# SOM_IO1.net
KiCad netlist of a schematic drawn in Altium Designer
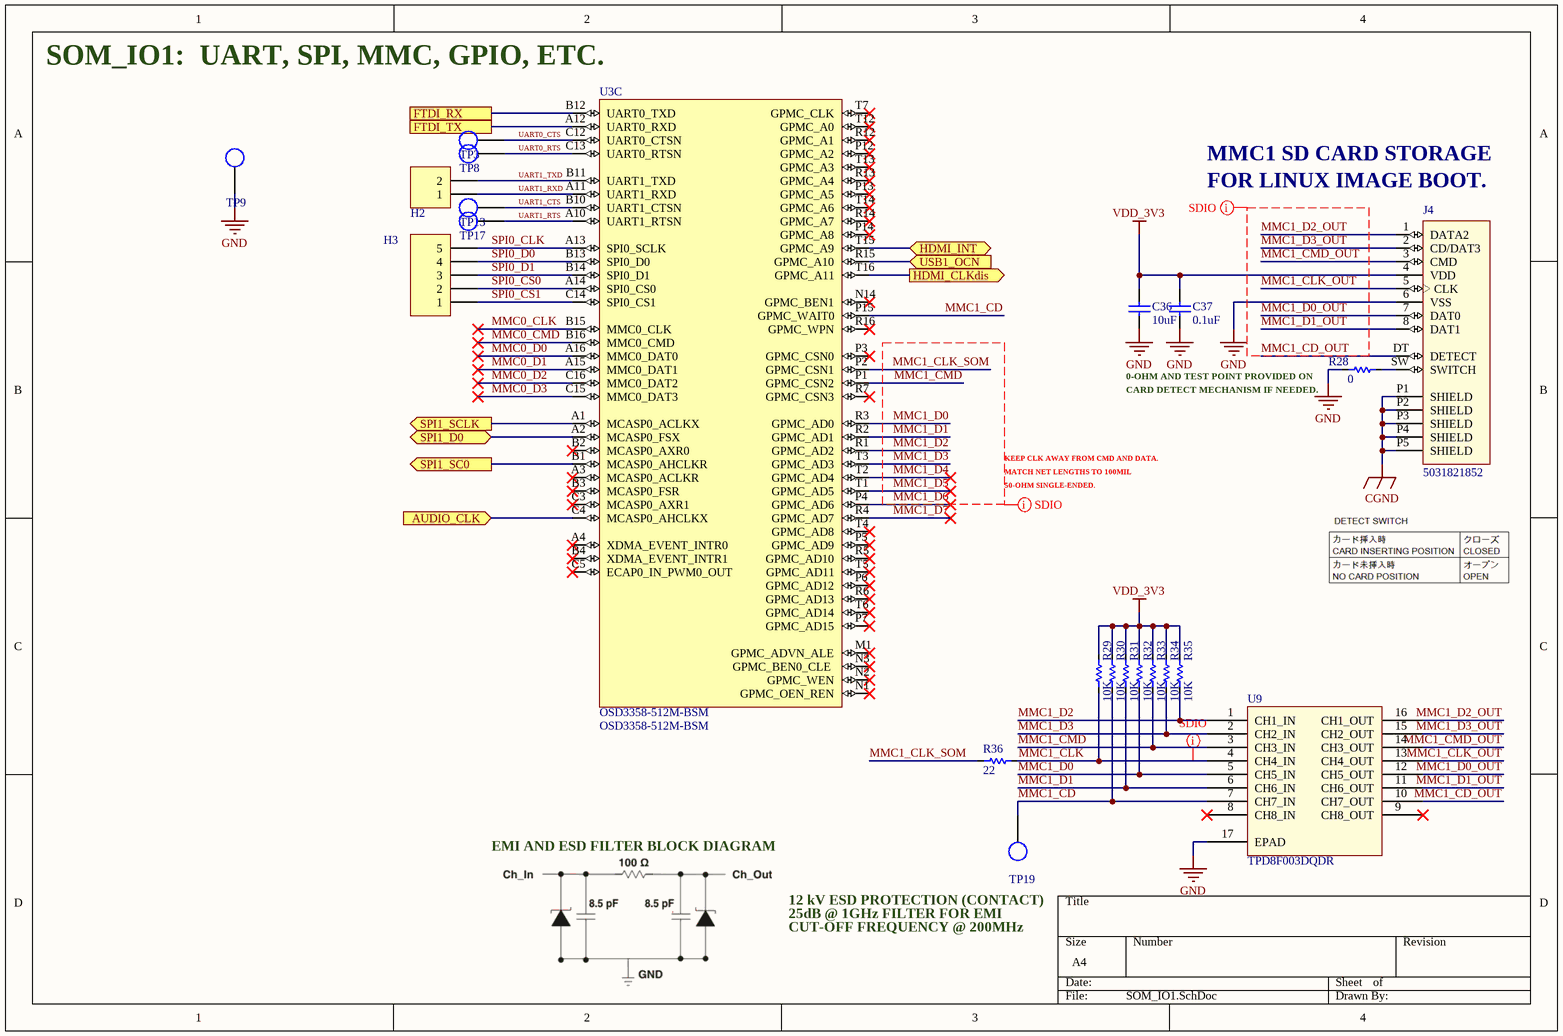
[diagram p0: SOM_IO1.SchDoc]

(export (version "E")
  (design (tool "Eeschema 10.0.6"))
  (components
    (comp (ref "C36")
      (value "10uF")
      (footprint "CAP_0603")
      (description "CAP CER 10UF 10V X5R 0603")
      (fields
        (field (name "MANUFACTURER") "KEMET")
        (field (name "MANUFACTURER PART NO.") "C0603C106M8PAC7867")
      )
      (libsource (lib "OSD335-X_Devboard") (part "C0603C106M8PAC7867"))
    )
    (comp (ref "C37")
      (value "0.1uF")
      (footprint "CAP_0603")
      (description "CAP CER 0.1UF 16V X7R 0603")
      (fields (field (name "MANUFACTURER") "KEMET") (field (name "MANUFACTURER PART NO.") "C0603C104M4RACTU"))
      (libsource (lib "OSD335-X_Devboard") (part "C0603C104M4RACTU"))
    )
    (comp (ref "H2")
      (value "02p")
      (footprint "HEADER_2X1_2.54MM")
      (description "CONN HEADER VERT 2POS 2.54MM")
      (fields
        (field (name "MANUFACTURER") "Wurth Elektronik")
        (field (name "MANUFACTURER PART NO.") "61300211121")
      )
      (libsource (lib "OSD335-X_Devboard") (part "61300211121"))
    )
    (comp (ref "H3")
      (value "06p")
      (footprint "HEADER_5X1_2.54MM")
      (description "CONN HEADER VERT 6POS 2.54MM")
      (fields
        (field (name "MANUFACTURER PART NO.") "61300511121")
        (field (name "MANUFACTURER") "Wurth Elektronik")
      )
      (libsource (lib "OSD335-X_Devboard") (part "61300511121"))
    )
    (comp (ref "J4")
      (value "5031821852")
      (footprint "5031821852")
      (description "MICRO SD NORMAL ULTRALOWPRO8CKTE")
      (fields (field (name "MANUFACTURER") "Molex"))
      (libsource (lib "OSD335-X_Devboard") (part "5031821852"))
    )
    (comp (ref "R28")
      (value "0")
      (footprint "RES_0603")
      (description "RES SMD 0 OHM JUMPER 1/10W 0603")
      (fields (field (name "MANUFACTURER") "Yageo") (field (name "MANUFACTURER PART NO.") "RC0603JR-070RL"))
      (libsource (lib "OSD335-X_Devboard") (part "RC0603JR-070RL"))
    )
    (comp (ref "R29")
      (value "10K")
      (footprint "RES_0603")
      (description "RES SMD 10K OHM 1% 1/10W 0603")
      (fields (field (name "TOLERANCE") "1%") (field (name "MANUFACTURER") "Yageo"))
      (libsource (lib "OSD335-X_Devboard") (part "RC0603FR-0710KL"))
    )
    (comp (ref "R30")
      (value "10K")
      (footprint "RES_0603")
      (description "RES SMD 10K OHM 1% 1/10W 0603")
      (fields (field (name "TOLERANCE") "1%") (field (name "MANUFACTURER") "Yageo"))
      (libsource (lib "OSD335-X_Devboard") (part "RC0603FR-0710KL"))
    )
    (comp (ref "R31")
      (value "10K")
      (footprint "RES_0603")
      (description "RES SMD 10K OHM 1% 1/10W 0603")
      (fields (field (name "TOLERANCE") "1%") (field (name "MANUFACTURER") "Yageo"))
      (libsource (lib "OSD335-X_Devboard") (part "RC0603FR-0710KL"))
    )
    (comp (ref "R32")
      (value "10K")
      (footprint "RES_0603")
      (description "RES SMD 10K OHM 1% 1/10W 0603")
      (fields (field (name "TOLERANCE") "1%") (field (name "MANUFACTURER") "Yageo"))
      (libsource (lib "OSD335-X_Devboard") (part "RC0603FR-0710KL"))
    )
    (comp (ref "R33")
      (value "10K")
      (footprint "RES_0603")
      (description "RES SMD 10K OHM 1% 1/10W 0603")
      (fields (field (name "TOLERANCE") "1%") (field (name "MANUFACTURER") "Yageo"))
      (libsource (lib "OSD335-X_Devboard") (part "RC0603FR-0710KL"))
    )
    (comp (ref "R34")
      (value "10K")
      (footprint "RES_0603")
      (description "RES SMD 10K OHM 1% 1/10W 0603")
      (fields (field (name "TOLERANCE") "1%") (field (name "MANUFACTURER") "Yageo"))
      (libsource (lib "OSD335-X_Devboard") (part "RC0603FR-0710KL"))
    )
    (comp (ref "R35")
      (value "10K")
      (footprint "RES_0603")
      (description "RES SMD 10K OHM 1% 1/10W 0603")
      (fields (field (name "TOLERANCE") "1%") (field (name "MANUFACTURER") "Yageo"))
      (libsource (lib "OSD335-X_Devboard") (part "RC0603FR-0710KL"))
    )
    (comp (ref "R36")
      (value "22")
      (footprint "RES_0603")
      (description "RES SMD 22 OHM 5% 1/10W 0603")
      (fields (field (name "TOLERANCE") "5%") (field (name "MANUFACTURER") "Yageo"))
      (libsource (lib "OSD335-X_Devboard") (part "RC0603JR-0722RL"))
    )
    (comp (ref "TP3")
      (value "TP_SMD")
      (footprint "TP_SMD")
      (libsource (lib "OSD335-X_Devboard") (part "TP_SMD"))
    )
    (comp (ref "TP8")
      (value "TP_SMD")
      (footprint "TP_SMD")
      (libsource (lib "OSD335-X_Devboard") (part "TP_SMD"))
    )
    (comp (ref "TP9")
      (value "TP_SMD")
      (footprint "TP_SMD")
      (libsource (lib "OSD335-X_Devboard") (part "TP_SMD"))
    )
    (comp (ref "TP13")
      (value "TP_SMD")
      (footprint "TP_SMD")
      (libsource (lib "OSD335-X_Devboard") (part "TP_SMD"))
    )
    (comp (ref "TP17")
      (value "TP_SMD")
      (footprint "TP_SMD")
      (libsource (lib "OSD335-X_Devboard") (part "TP_SMD"))
    )
    (comp (ref "TP19")
      (value "TP_SMD")
      (footprint "TP_SMD")
      (libsource (lib "OSD335-X_Devboard") (part "TP_SMD"))
    )
    (comp (ref "U3")
      (value "OSD3358-512M-BSM")
      (footprint "BGA256C127P16X16_2100X2100X308")
      (description "OSD3358-512M-BSM , 256-FBGA, 21mmx21mmx3mm")
      (fields (field (name "MANUFACTURER") "Octavo Systems") (field (name "PARTNUMBER") "OSD3358-512M-BSM"))
      (libsource (lib "OSD335-X_Devboard") (part "SOM-OSD3358-512M-BSM"))
    )
    (comp (ref "U9")
      (value "TPD8F003DQDR")
      (footprint "WSON-16_3.3MMX1.35MM")
      (description "FILTER RC(PI) 100 OHM/8.5PF SMD WITH ESD PROTECTION")
      (fields (field (name "MANUFACTURER") "Texas Instruments"))
      (libsource (lib "OSD335-X_Devboard") (part "TPD8F003DQDR"))
    )
  )
  (nets
    (net (code "1") (name "/AUDIO_CLK") (class "Default")
      (node (ref "U3") (pin "C4") (pinfunction "MCASP0_AHCLKX_C4") (pintype "bidirectional"))
    )
    (net (code "2") (name "/FTDI_RX") (class "Default")
      (node (ref "U3") (pin "B12") (pinfunction "UART0_TXD_B12") (pintype "bidirectional"))
    )
    (net (code "3") (name "/FTDI_TX") (class "Default")
      (node (ref "U3") (pin "A12") (pinfunction "UART0_RXD_A12") (pintype "bidirectional"))
    )
    (net (code "4") (name "/HDMI_CLKdis") (class "Default")
      (node (ref "U3") (pin "T16") (pinfunction "GPMC_A11_T16") (pintype "bidirectional"))
    )
    (net (code "5") (name "/HDMI_INT") (class "Default")
      (node (ref "U3") (pin "T15") (pinfunction "GPMC_A9_T15") (pintype "bidirectional"))
    )
    (net (code "6") (name "/MMC0_CLK") (class "Default")
      (node (ref "U3") (pin "B15") (pinfunction "MMC0_CLK_B15") (pintype "bidirectional+no_connect"))
    )
    (net (code "7") (name "/MMC0_CMD") (class "Default")
      (node (ref "U3") (pin "B16") (pinfunction "MMC0_CMD_B16") (pintype "bidirectional+no_connect"))
    )
    (net (code "8") (name "/MMC0_D0") (class "Default")
      (node (ref "U3") (pin "A16") (pinfunction "MMC0_DAT0_A16") (pintype "bidirectional+no_connect"))
    )
    (net (code "9") (name "/MMC0_D1") (class "Default")
      (node (ref "U3") (pin "A15") (pinfunction "MMC0_DAT1_A15") (pintype "bidirectional+no_connect"))
    )
    (net (code "10") (name "/MMC0_D2") (class "Default")
      (node (ref "U3") (pin "C16") (pinfunction "MMC0_DAT2_C16") (pintype "bidirectional+no_connect"))
    )
    (net (code "11") (name "/MMC0_D3") (class "Default")
      (node (ref "U3") (pin "C15") (pinfunction "MMC0_DAT3_C15") (pintype "bidirectional+no_connect"))
    )
    (net (code "12") (name "/MMC1_CD") (class "Default")
      (node (ref "R30") (pin "1") (pinfunction "1_1") (pintype "passive"))
      (node (ref "TP19") (pin "1") (pinfunction "1_1") (pintype "passive"))
      (node (ref "U3") (pin "P15") (pinfunction "GPMC_WAIT0_P15") (pintype "bidirectional"))
      (node (ref "U9") (pin "7") (pinfunction "CH7_IN_7") (pintype "passive"))
    )
    (net (code "13") (name "/MMC1_CD_OUT") (class "Default")
      (node (ref "J4") (pin "DT") (pinfunction "DETECT_DT") (pintype "bidirectional"))
      (node (ref "U9") (pin "10") (pinfunction "CH7_OUT_10") (pintype "passive"))
    )
    (net (code "14") (name "/MMC1_CLK") (class "Default")
      (node (ref "R29") (pin "1") (pinfunction "1_1") (pintype "passive"))
      (node (ref "R36") (pin "2") (pinfunction "2_2") (pintype "passive"))
      (node (ref "U9") (pin "4") (pinfunction "CH4_IN_4") (pintype "passive"))
    )
    (net (code "15") (name "/MMC1_CLK_OUT") (class "Default")
      (node (ref "J4") (pin "5") (pinfunction "CLK_5") (pintype "bidirectional"))
      (node (ref "U9") (pin "13") (pinfunction "CH4_OUT_13") (pintype "passive"))
    )
    (net (code "16") (name "/MMC1_CLK_SOM") (class "Default")
      (node (ref "R36") (pin "1") (pinfunction "1_1") (pintype "passive"))
      (node (ref "U3") (pin "P2") (pinfunction "GPMC_CSN1_P2") (pintype "bidirectional"))
    )
    (net (code "17") (name "/MMC1_CMD") (class "Default")
      (node (ref "R33") (pin "1") (pinfunction "1_1") (pintype "passive"))
      (node (ref "U3") (pin "P1") (pinfunction "GPMC_CSN2_P1") (pintype "bidirectional"))
      (node (ref "U9") (pin "3") (pinfunction "CH3_IN_3") (pintype "passive"))
    )
    (net (code "18") (name "/MMC1_CMD_OUT") (class "Default")
      (node (ref "J4") (pin "3") (pinfunction "CMD_3") (pintype "bidirectional"))
      (node (ref "U9") (pin "14") (pinfunction "CH3_OUT_14") (pintype "passive"))
    )
    (net (code "19") (name "/MMC1_D0") (class "Default")
      (node (ref "R32") (pin "1") (pinfunction "1_1") (pintype "passive"))
      (node (ref "U3") (pin "R3") (pinfunction "GPMC_AD0_R3") (pintype "bidirectional"))
      (node (ref "U9") (pin "5") (pinfunction "CH5_IN_5") (pintype "passive"))
    )
    (net (code "20") (name "/MMC1_D0_OUT") (class "Default")
      (node (ref "J4") (pin "7") (pinfunction "DAT0_7") (pintype "bidirectional"))
      (node (ref "U9") (pin "12") (pinfunction "CH5_OUT_12") (pintype "passive"))
    )
    (net (code "21") (name "/MMC1_D1") (class "Default")
      (node (ref "R31") (pin "1") (pinfunction "1_1") (pintype "passive"))
      (node (ref "U3") (pin "R2") (pinfunction "GPMC_AD1_R2") (pintype "bidirectional"))
      (node (ref "U9") (pin "6") (pinfunction "CH6_IN_6") (pintype "passive"))
    )
    (net (code "22") (name "/MMC1_D1_OUT") (class "Default")
      (node (ref "J4") (pin "8") (pinfunction "DAT1_8") (pintype "bidirectional"))
      (node (ref "U9") (pin "11") (pinfunction "CH6_OUT_11") (pintype "passive"))
    )
    (net (code "23") (name "/MMC1_D2") (class "Default")
      (node (ref "R35") (pin "1") (pinfunction "1_1") (pintype "passive"))
      (node (ref "U3") (pin "R1") (pinfunction "GPMC_AD2_R1") (pintype "bidirectional"))
      (node (ref "U9") (pin "1") (pinfunction "CH1_IN_1") (pintype "passive"))
    )
    (net (code "24") (name "/MMC1_D2_OUT") (class "Default")
      (node (ref "J4") (pin "1") (pinfunction "DATA2_1") (pintype "bidirectional"))
      (node (ref "U9") (pin "16") (pinfunction "CH1_OUT_16") (pintype "passive"))
    )
    (net (code "25") (name "/MMC1_D3") (class "Default")
      (node (ref "R34") (pin "1") (pinfunction "1_1") (pintype "passive"))
      (node (ref "U3") (pin "T3") (pinfunction "GPMC_AD3_T3") (pintype "bidirectional"))
      (node (ref "U9") (pin "2") (pinfunction "CH2_IN_2") (pintype "passive"))
    )
    (net (code "26") (name "/MMC1_D3_OUT") (class "Default")
      (node (ref "J4") (pin "2") (pinfunction "CD/DAT3_2") (pintype "bidirectional"))
      (node (ref "U9") (pin "15") (pinfunction "CH2_OUT_15") (pintype "passive"))
    )
    (net (code "27") (name "/MMC1_D4") (class "Default")
      (node (ref "U3") (pin "T2") (pinfunction "GPMC_AD4_T2") (pintype "bidirectional+no_connect"))
    )
    (net (code "28") (name "/MMC1_D5") (class "Default")
      (node (ref "U3") (pin "T1") (pinfunction "GPMC_AD5_T1") (pintype "bidirectional+no_connect"))
    )
    (net (code "29") (name "/MMC1_D6") (class "Default")
      (node (ref "U3") (pin "P4") (pinfunction "GPMC_AD6_P4") (pintype "bidirectional+no_connect"))
    )
    (net (code "30") (name "/MMC1_D7") (class "Default")
      (node (ref "U3") (pin "R4") (pinfunction "GPMC_AD7_R4") (pintype "bidirectional+no_connect"))
    )
    (net (code "31") (name "/SPI0_CLK") (class "Default")
      (node (ref "H3") (pin "5") (pinfunction "5_5") (pintype "passive"))
      (node (ref "U3") (pin "A13") (pinfunction "SPI0_SCLK_A13") (pintype "bidirectional"))
    )
    (net (code "32") (name "/SPI0_CS0") (class "Default")
      (node (ref "H3") (pin "2") (pinfunction "2_2") (pintype "passive"))
      (node (ref "U3") (pin "A14") (pinfunction "SPI0_CS0_A14") (pintype "bidirectional"))
    )
    (net (code "33") (name "/SPI0_CS1") (class "Default")
      (node (ref "H3") (pin "1") (pinfunction "1_1") (pintype "passive"))
      (node (ref "U3") (pin "C14") (pinfunction "SPI0_CS1_C14") (pintype "bidirectional"))
    )
    (net (code "34") (name "/SPI0_D0") (class "Default")
      (node (ref "H3") (pin "4") (pinfunction "4_4") (pintype "passive"))
      (node (ref "U3") (pin "B13") (pinfunction "SPI0_D0_B13") (pintype "bidirectional"))
    )
    (net (code "35") (name "/SPI0_D1") (class "Default")
      (node (ref "H3") (pin "3") (pinfunction "3_3") (pintype "passive"))
      (node (ref "U3") (pin "B14") (pinfunction "SPI0_D1_B14") (pintype "bidirectional"))
    )
    (net (code "36") (name "/SPI1_D0") (class "Default")
      (node (ref "U3") (pin "A2") (pinfunction "MCASP0_FSX_A2") (pintype "bidirectional"))
    )
    (net (code "37") (name "/SPI1_SC0") (class "Default")
      (node (ref "U3") (pin "B1") (pinfunction "MCASP0_AHCLKR_B1") (pintype "bidirectional"))
    )
    (net (code "38") (name "/SPI1_SCLK") (class "Default")
      (node (ref "U3") (pin "A1") (pinfunction "MCASP0_ACLKX_A1") (pintype "bidirectional"))
    )
    (net (code "39") (name "/UART0_CTS") (class "Default")
      (node (ref "TP3") (pin "1") (pinfunction "1_1") (pintype "passive"))
      (node (ref "U3") (pin "C12") (pinfunction "UART0_CTSN_C12") (pintype "bidirectional"))
    )
    (net (code "40") (name "/UART0_RTS") (class "Default")
      (node (ref "TP8") (pin "1") (pinfunction "1_1") (pintype "passive"))
      (node (ref "U3") (pin "C13") (pinfunction "UART0_RTSN_C13") (pintype "bidirectional"))
    )
    (net (code "41") (name "/UART1_CTS") (class "Default")
      (node (ref "TP13") (pin "1") (pinfunction "1_1") (pintype "passive"))
      (node (ref "U3") (pin "B10") (pinfunction "UART1_CTSN_B10") (pintype "bidirectional"))
    )
    (net (code "42") (name "/UART1_RTS") (class "Default")
      (node (ref "TP17") (pin "1") (pinfunction "1_1") (pintype "passive"))
      (node (ref "U3") (pin "A10") (pinfunction "UART1_RTSN_A10") (pintype "bidirectional"))
    )
    (net (code "43") (name "/UART1_RXD") (class "Default")
      (node (ref "H2") (pin "1") (pinfunction "1_1") (pintype "passive"))
      (node (ref "U3") (pin "A11") (pinfunction "UART1_RXD_A11") (pintype "bidirectional"))
    )
    (net (code "44") (name "/UART1_TXD") (class "Default")
      (node (ref "H2") (pin "2") (pinfunction "2_2") (pintype "passive"))
      (node (ref "U3") (pin "B11") (pinfunction "UART1_TXD_B11") (pintype "bidirectional"))
    )
    (net (code "45") (name "/USB1_OCN") (class "Default")
      (node (ref "U3") (pin "R15") (pinfunction "GPMC_A10_R15") (pintype "bidirectional"))
    )
    (net (code "46") (name "CGND") (class "Default")
      (node (ref "J4") (pin "P1") (pinfunction "SHIELD_P1") (pintype "passive"))
      (node (ref "J4") (pin "P2") (pinfunction "SHIELD_P2") (pintype "passive"))
      (node (ref "J4") (pin "P3") (pinfunction "SHIELD_P3") (pintype "passive"))
      (node (ref "J4") (pin "P4") (pinfunction "SHIELD_P4") (pintype "passive"))
      (node (ref "J4") (pin "P5") (pinfunction "SHIELD_P5") (pintype "passive"))
    )
    (net (code "47") (name "GND") (class "Default")
      (node (ref "C36") (pin "1") (pinfunction "1_1") (pintype "passive"))
      (node (ref "C37") (pin "1") (pinfunction "1_1") (pintype "passive"))
      (node (ref "J4") (pin "6") (pinfunction "VSS_6") (pintype "power_in"))
      (node (ref "R28") (pin "1") (pinfunction "1_1") (pintype "passive"))
      (node (ref "TP9") (pin "1") (pinfunction "1_1") (pintype "passive"))
      (node (ref "U9") (pin "17") (pinfunction "EPAD_17") (pintype "power_in"))
    )
    (net (code "48") (name "Net-(J4-SWITCH)") (class "Default")
      (node (ref "J4") (pin "SW") (pinfunction "SWITCH_SW") (pintype "bidirectional"))
      (node (ref "R28") (pin "2") (pinfunction "2_2") (pintype "passive"))
    )
    (net (code "49") (name "VDD_3V3") (class "Default")
      (node (ref "C36") (pin "2") (pinfunction "2_2") (pintype "passive"))
      (node (ref "C37") (pin "2") (pinfunction "2_2") (pintype "passive"))
      (node (ref "J4") (pin "4") (pinfunction "VDD_4") (pintype "power_in"))
      (node (ref "R29") (pin "2") (pinfunction "2_2") (pintype "passive"))
      (node (ref "R30") (pin "2") (pinfunction "2_2") (pintype "passive"))
      (node (ref "R31") (pin "2") (pinfunction "2_2") (pintype "passive"))
      (node (ref "R32") (pin "2") (pinfunction "2_2") (pintype "passive"))
      (node (ref "R33") (pin "2") (pinfunction "2_2") (pintype "passive"))
      (node (ref "R34") (pin "2") (pinfunction "2_2") (pintype "passive"))
      (node (ref "R35") (pin "2") (pinfunction "2_2") (pintype "passive"))
    )
    (net (code "50") (name "unconnected-(U3C-ECAP0_IN_PWM0_OUT-PadC5)") (class "Default")
      (node (ref "U3") (pin "C5") (pinfunction "ECAP0_IN_PWM0_OUT_C5") (pintype "bidirectional+no_connect"))
    )
    (net (code "51") (name "unconnected-(U3C-GPMC_A0-PadT12)") (class "Default")
      (node (ref "U3") (pin "T12") (pinfunction "GPMC_A0_T12") (pintype "bidirectional+no_connect"))
    )
    (net (code "52") (name "unconnected-(U3C-GPMC_A1-PadR12)") (class "Default")
      (node (ref "U3") (pin "R12") (pinfunction "GPMC_A1_R12") (pintype "bidirectional+no_connect"))
    )
    (net (code "53") (name "unconnected-(U3C-GPMC_A2-PadP12)") (class "Default")
      (node (ref "U3") (pin "P12") (pinfunction "GPMC_A2_P12") (pintype "bidirectional+no_connect"))
    )
    (net (code "54") (name "unconnected-(U3C-GPMC_A3-PadT13)") (class "Default")
      (node (ref "U3") (pin "T13") (pinfunction "GPMC_A3_T13") (pintype "bidirectional+no_connect"))
    )
    (net (code "55") (name "unconnected-(U3C-GPMC_A4-PadR13)") (class "Default")
      (node (ref "U3") (pin "R13") (pinfunction "GPMC_A4_R13") (pintype "bidirectional+no_connect"))
    )
    (net (code "56") (name "unconnected-(U3C-GPMC_A5-PadP13)") (class "Default")
      (node (ref "U3") (pin "P13") (pinfunction "GPMC_A5_P13") (pintype "bidirectional+no_connect"))
    )
    (net (code "57") (name "unconnected-(U3C-GPMC_A6-PadT14)") (class "Default")
      (node (ref "U3") (pin "T14") (pinfunction "GPMC_A6_T14") (pintype "bidirectional+no_connect"))
    )
    (net (code "58") (name "unconnected-(U3C-GPMC_A7-PadR14)") (class "Default")
      (node (ref "U3") (pin "R14") (pinfunction "GPMC_A7_R14") (pintype "bidirectional+no_connect"))
    )
    (net (code "59") (name "unconnected-(U3C-GPMC_A8-PadP14)") (class "Default")
      (node (ref "U3") (pin "P14") (pinfunction "GPMC_A8_P14") (pintype "bidirectional+no_connect"))
    )
    (net (code "60") (name "unconnected-(U3C-GPMC_AD8-PadT4)") (class "Default")
      (node (ref "U3") (pin "T4") (pinfunction "GPMC_AD8_T4") (pintype "bidirectional+no_connect"))
    )
    (net (code "61") (name "unconnected-(U3C-GPMC_AD9-PadP5)") (class "Default")
      (node (ref "U3") (pin "P5") (pinfunction "GPMC_AD9_P5") (pintype "bidirectional+no_connect"))
    )
    (net (code "62") (name "unconnected-(U3C-GPMC_AD10-PadR5)") (class "Default")
      (node (ref "U3") (pin "R5") (pinfunction "GPMC_AD10_R5") (pintype "bidirectional+no_connect"))
    )
    (net (code "63") (name "unconnected-(U3C-GPMC_AD11-PadT5)") (class "Default")
      (node (ref "U3") (pin "T5") (pinfunction "GPMC_AD11_T5") (pintype "bidirectional+no_connect"))
    )
    (net (code "64") (name "unconnected-(U3C-GPMC_AD12-PadP6)") (class "Default")
      (node (ref "U3") (pin "P6") (pinfunction "GPMC_AD12_P6") (pintype "bidirectional+no_connect"))
    )
    (net (code "65") (name "unconnected-(U3C-GPMC_AD13-PadR6)") (class "Default")
      (node (ref "U3") (pin "R6") (pinfunction "GPMC_AD13_R6") (pintype "bidirectional+no_connect"))
    )
    (net (code "66") (name "unconnected-(U3C-GPMC_AD14-PadT6)") (class "Default")
      (node (ref "U3") (pin "T6") (pinfunction "GPMC_AD14_T6") (pintype "bidirectional+no_connect"))
    )
    (net (code "67") (name "unconnected-(U3C-GPMC_AD15-PadP7)") (class "Default")
      (node (ref "U3") (pin "P7") (pinfunction "GPMC_AD15_P7") (pintype "bidirectional+no_connect"))
    )
    (net (code "68") (name "unconnected-(U3C-GPMC_ADVN_ALE-PadM1)") (class "Default")
      (node (ref "U3") (pin "M1") (pinfunction "GPMC_ADVN_ALE_M1") (pintype "bidirectional+no_connect"))
    )
    (net (code "69") (name "unconnected-(U3C-GPMC_BEN0_CLE-PadN3)") (class "Default")
      (node (ref "U3") (pin "N3") (pinfunction "GPMC_BEN0_CLE_N3") (pintype "bidirectional+no_connect"))
    )
    (net (code "70") (name "unconnected-(U3C-GPMC_BEN1-PadN14)") (class "Default")
      (node (ref "U3") (pin "N14") (pinfunction "GPMC_BEN1_N14") (pintype "bidirectional+no_connect"))
    )
    (net (code "71") (name "unconnected-(U3C-GPMC_CLK-PadT7)") (class "Default")
      (node (ref "U3") (pin "T7") (pinfunction "GPMC_CLK_T7") (pintype "bidirectional+no_connect"))
    )
    (net (code "72") (name "unconnected-(U3C-GPMC_CSN0-PadP3)") (class "Default")
      (node (ref "U3") (pin "P3") (pinfunction "GPMC_CSN0_P3") (pintype "bidirectional+no_connect"))
    )
    (net (code "73") (name "unconnected-(U3C-GPMC_CSN3-PadR7)") (class "Default")
      (node (ref "U3") (pin "R7") (pinfunction "GPMC_CSN3_R7") (pintype "bidirectional+no_connect"))
    )
    (net (code "74") (name "unconnected-(U3C-GPMC_OEN_REN-PadN1)") (class "Default")
      (node (ref "U3") (pin "N1") (pinfunction "GPMC_OEN_REN_N1") (pintype "bidirectional+no_connect"))
    )
    (net (code "75") (name "unconnected-(U3C-GPMC_WEN-PadN2)") (class "Default")
      (node (ref "U3") (pin "N2") (pinfunction "GPMC_WEN_N2") (pintype "bidirectional+no_connect"))
    )
    (net (code "76") (name "unconnected-(U3C-GPMC_WPN-PadR16)") (class "Default")
      (node (ref "U3") (pin "R16") (pinfunction "GPMC_WPN_R16") (pintype "bidirectional+no_connect"))
    )
    (net (code "77") (name "unconnected-(U3C-MCASP0_ACLKR-PadA3)") (class "Default")
      (node (ref "U3") (pin "A3") (pinfunction "MCASP0_ACLKR_A3") (pintype "bidirectional+no_connect"))
    )
    (net (code "78") (name "unconnected-(U3C-MCASP0_AXR0-PadB2)") (class "Default")
      (node (ref "U3") (pin "B2") (pinfunction "MCASP0_AXR0_B2") (pintype "bidirectional+no_connect"))
    )
    (net (code "79") (name "unconnected-(U3C-MCASP0_AXR1-PadC3)") (class "Default")
      (node (ref "U3") (pin "C3") (pinfunction "MCASP0_AXR1_C3") (pintype "bidirectional+no_connect"))
    )
    (net (code "80") (name "unconnected-(U3C-MCASP0_FSR-PadB3)") (class "Default")
      (node (ref "U3") (pin "B3") (pinfunction "MCASP0_FSR_B3") (pintype "bidirectional+no_connect"))
    )
    (net (code "81") (name "unconnected-(U3C-XDMA_EVENT_INTR0-PadA4)") (class "Default")
      (node (ref "U3") (pin "A4") (pinfunction "XDMA_EVENT_INTR0_A4") (pintype "bidirectional+no_connect"))
    )
    (net (code "82") (name "unconnected-(U3C-XDMA_EVENT_INTR1-PadB4)") (class "Default")
      (node (ref "U3") (pin "B4") (pinfunction "XDMA_EVENT_INTR1_B4") (pintype "bidirectional+no_connect"))
    )
    (net (code "83") (name "unconnected-(U9-CH8_IN-Pad8)") (class "Default")
      (node (ref "U9") (pin "8") (pinfunction "CH8_IN_8") (pintype "passive+no_connect"))
    )
    (net (code "84") (name "unconnected-(U9-CH8_OUT-Pad9)") (class "Default")
      (node (ref "U9") (pin "9") (pinfunction "CH8_OUT_9") (pintype "passive+no_connect"))
    )
  )
)
